# Servo_motor_controller.net
KiCad netlist of a schematic drawn in EAGLE
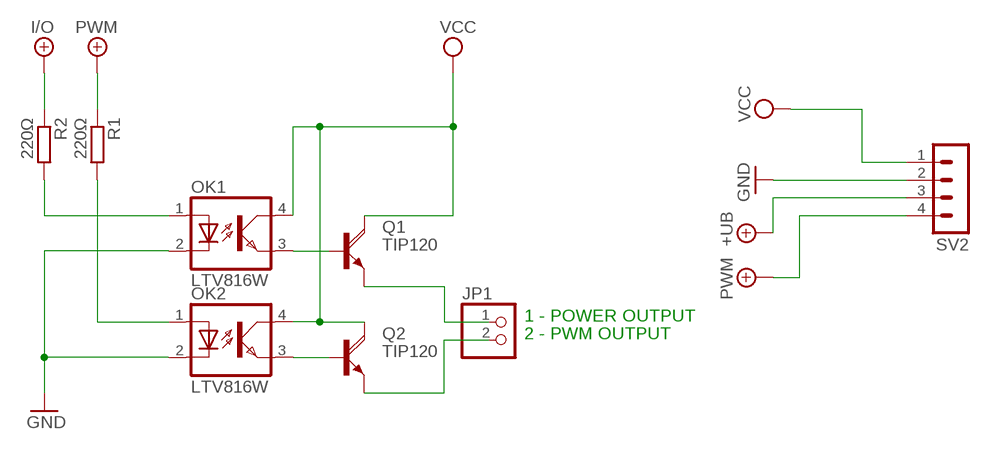
[diagram p0: schematic, sheet 1]

(export (version "E")
  (design (tool "Eeschema 10.0.6"))
  (components
    (comp (ref "JP1")
      (value "PINHD-1X2")
      (footprint "eagle-import:1X02")
      (libsource (lib "eagle-import") (part "PINHD-1X2"))
    )
    (comp (ref "OK1")
      (value "LTV816W")
      (footprint "eagle-import:DIL4-SMD")
      (libsource (lib "eagle-import") (part "LTV816W"))
    )
    (comp (ref "OK2")
      (value "LTV816W")
      (footprint "eagle-import:DIL4-SMD")
      (libsource (lib "eagle-import") (part "LTV816W"))
    )
    (comp (ref "Q1")
      (value "TIP120")
      (footprint "eagle-import:TO220AH")
      (libsource (lib "eagle-import") (part "TIP120"))
    )
    (comp (ref "Q2")
      (value "TIP120")
      (footprint "eagle-import:TO220AH")
      (libsource (lib "eagle-import") (part "TIP120"))
    )
    (comp (ref "R1")
      (value "220Ω")
      (footprint "eagle-import:0207_10")
      (libsource (lib "eagle-import") (part "R-EU_0207/10"))
    )
    (comp (ref "R2")
      (value "220Ω")
      (footprint "eagle-import:0207_10")
      (libsource (lib "eagle-import") (part "R-EU_0207/10"))
    )
    (comp (ref "SV2")
      (value "MA04-1")
      (footprint "eagle-import:MA04-1")
      (libsource (lib "eagle-import") (part "MA04-1"))
    )
  )
  (nets
    (net (code "1") (name "+UB") (class "Default")
      (node (ref "R2") (pin "1") (pinfunction "1_1") (pintype "passive"))
      (node (ref "SV2") (pin "3") (pinfunction "3_3") (pintype "passive"))
    )
    (net (code "2") (name "GND") (class "Default")
      (node (ref "OK1") (pin "2") (pinfunction "C_2") (pintype "passive"))
      (node (ref "OK2") (pin "2") (pinfunction "C_2") (pintype "passive"))
      (node (ref "SV2") (pin "2") (pinfunction "2_2") (pintype "passive"))
    )
    (net (code "3") (name "Net-(JP1-Pad1)") (class "Default")
      (node (ref "JP1") (pin "1") (pinfunction "1_1") (pintype "passive"))
      (node (ref "Q1") (pin "E") (pinfunction "E_E") (pintype "passive"))
    )
    (net (code "4") (name "Net-(JP1-Pad2)") (class "Default")
      (node (ref "JP1") (pin "2") (pinfunction "2_2") (pintype "passive"))
      (node (ref "Q2") (pin "E") (pinfunction "E_E") (pintype "passive"))
    )
    (net (code "5") (name "Net-(OK1-A)") (class "Default")
      (node (ref "OK1") (pin "1") (pinfunction "A_1") (pintype "passive"))
      (node (ref "R2") (pin "2") (pinfunction "2_2") (pintype "passive"))
    )
    (net (code "6") (name "Net-(OK1-EMIT)") (class "Default")
      (node (ref "OK1") (pin "3") (pinfunction "EMIT_3") (pintype "passive"))
      (node (ref "Q1") (pin "B") (pinfunction "B_B") (pintype "passive"))
    )
    (net (code "7") (name "Net-(OK2-A)") (class "Default")
      (node (ref "OK2") (pin "1") (pinfunction "A_1") (pintype "passive"))
      (node (ref "R1") (pin "2") (pinfunction "2_2") (pintype "passive"))
    )
    (net (code "8") (name "Net-(OK2-EMIT)") (class "Default")
      (node (ref "OK2") (pin "3") (pinfunction "EMIT_3") (pintype "passive"))
      (node (ref "Q2") (pin "B") (pinfunction "B_B") (pintype "passive"))
    )
    (net (code "9") (name "PWM") (class "Default")
      (node (ref "R1") (pin "1") (pinfunction "1_1") (pintype "passive"))
      (node (ref "SV2") (pin "4") (pinfunction "4_4") (pintype "passive"))
    )
    (net (code "10") (name "VCC") (class "Default")
      (node (ref "OK1") (pin "4") (pinfunction "COL_4") (pintype "passive"))
      (node (ref "OK2") (pin "4") (pinfunction "COL_4") (pintype "passive"))
      (node (ref "Q1") (pin "C") (pinfunction "C_C") (pintype "passive"))
      (node (ref "Q2") (pin "C") (pinfunction "C_C") (pintype "passive"))
      (node (ref "SV2") (pin "1") (pinfunction "1_1") (pintype "passive"))
    )
  )
)
